# ferminator2000.net
KiCad netlist of a schematic drawn in EAGLE
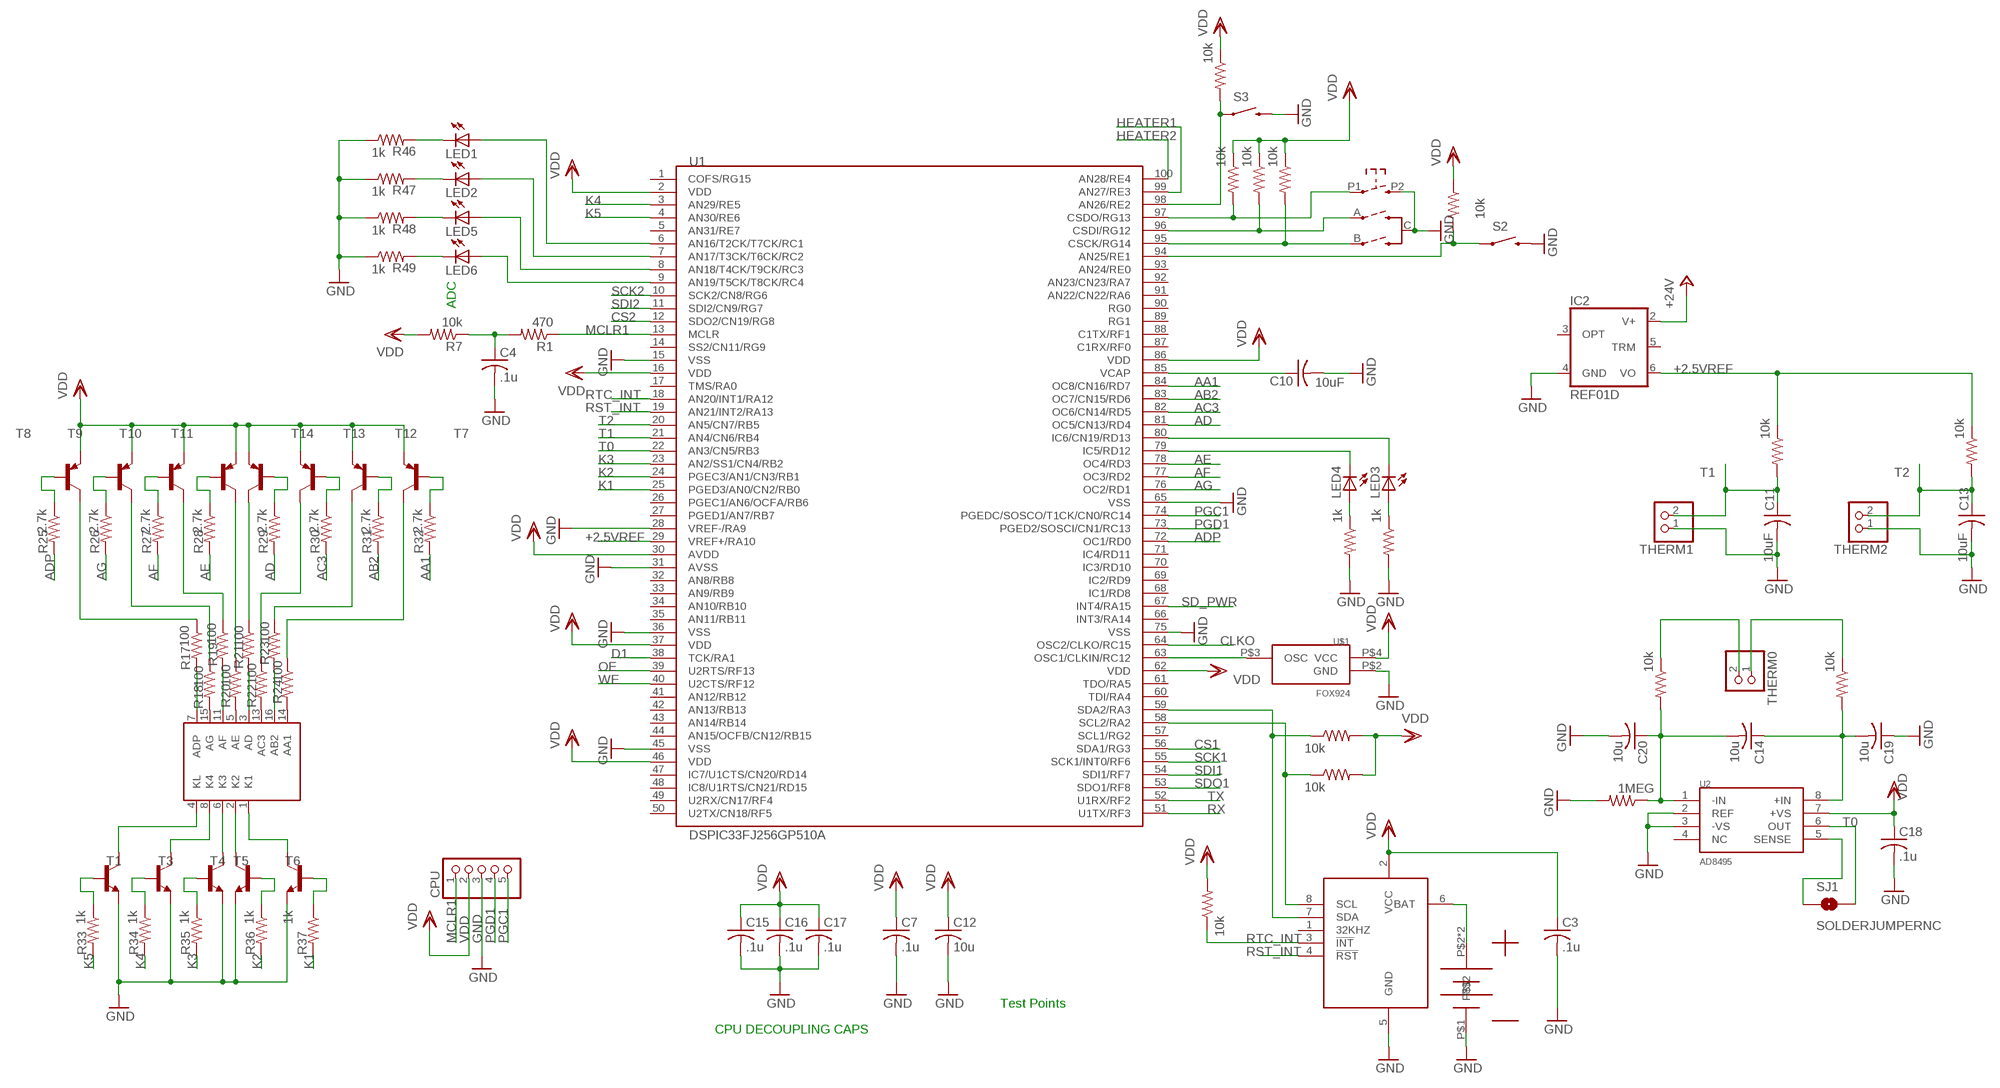
[diagram p0: schematic, sheet 1]
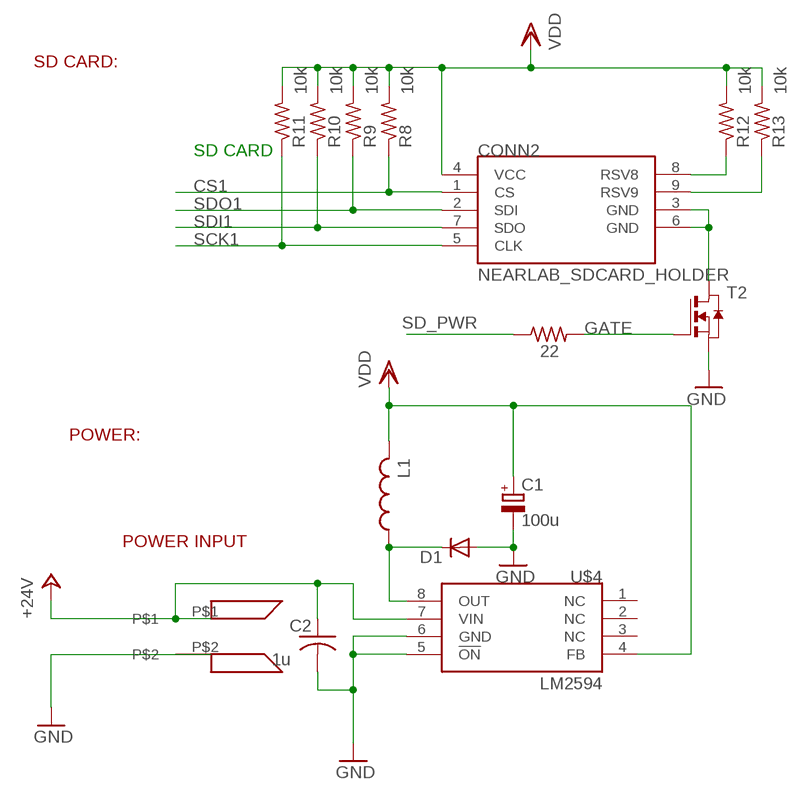
[diagram p1: schematic, sheet 2]
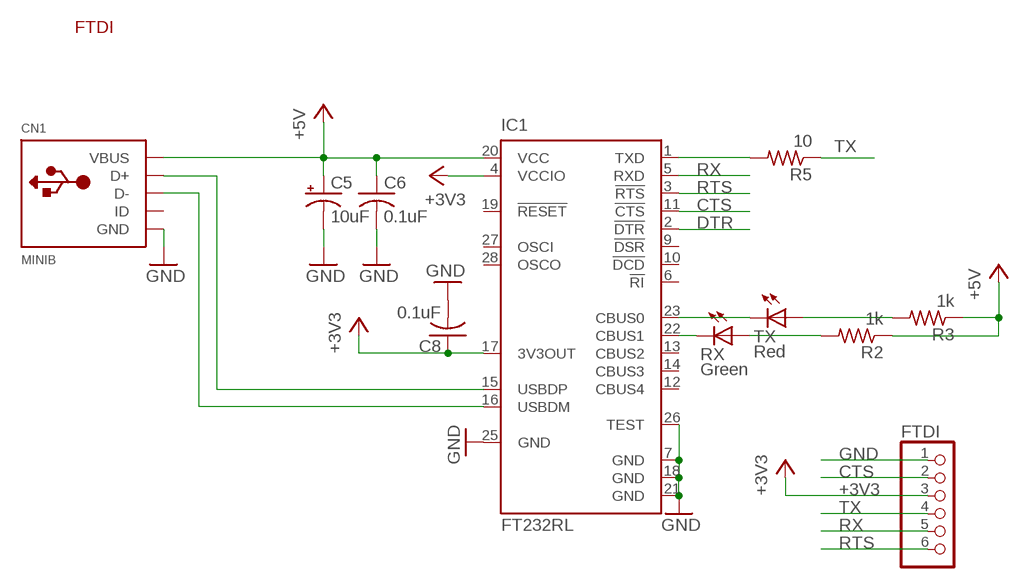
[diagram p2: schematic, sheet 3]
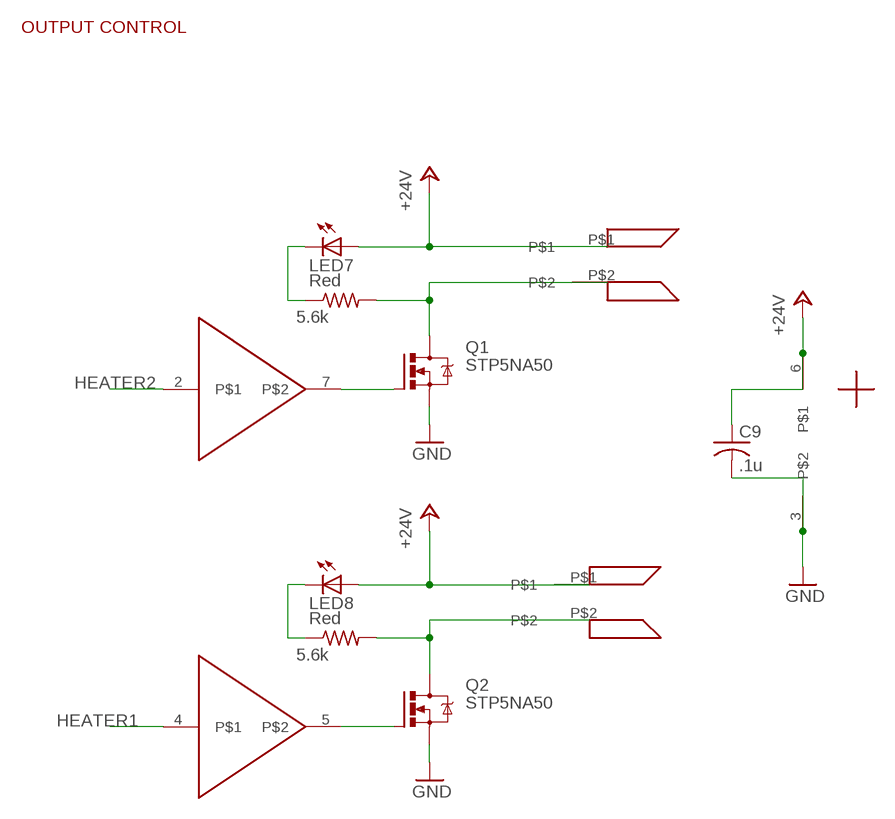
[diagram p3: schematic, sheet 4]

(export (version "E")
  (design (tool "Eeschema 10.0.6"))
  (components
    (comp (ref "C3")
      (value ".1u")
      (footprint "eagle-import:C0603")
      (libsource (lib "eagle-import") (part "rcl_C-USC0603"))
    )
    (comp (ref "C4")
      (value ".1u")
      (footprint "eagle-import:C0603")
      (libsource (lib "eagle-import") (part "rcl_C-USC0603"))
    )
    (comp (ref "C7")
      (value ".1u")
      (footprint "eagle-import:C0603")
      (libsource (lib "eagle-import") (part "rcl_C-USC0603"))
    )
    (comp (ref "C10")
      (value "10uF")
      (footprint "eagle-import:C0805")
      (libsource (lib "eagle-import") (part "rcl_C-USC0805"))
    )
    (comp (ref "C11")
      (value "10uF")
      (footprint "eagle-import:C0805")
      (libsource (lib "eagle-import") (part "rcl_C-USC0805"))
    )
    (comp (ref "C12")
      (value "10u")
      (footprint "eagle-import:C0805")
      (libsource (lib "eagle-import") (part "rcl_C-USC0805"))
    )
    (comp (ref "C13")
      (value "10uF")
      (footprint "eagle-import:C0805")
      (libsource (lib "eagle-import") (part "rcl_C-USC0805"))
    )
    (comp (ref "C14")
      (value "10u")
      (footprint "eagle-import:C0603")
      (libsource (lib "eagle-import") (part "rcl_C-USC0603"))
    )
    (comp (ref "C15")
      (value ".1u")
      (footprint "eagle-import:C0603")
      (libsource (lib "eagle-import") (part "rcl_C-USC0603"))
    )
    (comp (ref "C16")
      (value ".1u")
      (footprint "eagle-import:C0603")
      (libsource (lib "eagle-import") (part "rcl_C-USC0603"))
    )
    (comp (ref "C17")
      (value ".1u")
      (footprint "eagle-import:C0603")
      (libsource (lib "eagle-import") (part "rcl_C-USC0603"))
    )
    (comp (ref "C18")
      (value ".1u")
      (footprint "eagle-import:C0603")
      (libsource (lib "eagle-import") (part "rcl_C-USC0603"))
    )
    (comp (ref "C19")
      (value "10u")
      (footprint "eagle-import:C0603")
      (libsource (lib "eagle-import") (part "rcl_C-USC0603"))
    )
    (comp (ref "C20")
      (value "10u")
      (footprint "eagle-import:C0603")
      (libsource (lib "eagle-import") (part "rcl_C-USC0603"))
    )
    (comp (ref "CPU")
      (value "PINHD-1X5")
      (footprint "eagle-import:1X05")
      (libsource (lib "eagle-import") (part "PINHD-1X5"))
    )
    (comp (ref "IC2")
      (value "REF01D")
      (footprint "eagle-import:SO08")
      (libsource (lib "eagle-import") (part "REF01D"))
    )
    (comp (ref "LED1")
      (value "LEDCHIP-LED0805")
      (footprint "eagle-import:CHIP-LED0805")
      (libsource (lib "eagle-import") (part "led_LEDCHIP-LED0805"))
    )
    (comp (ref "LED2")
      (value "LEDCHIP-LED0805")
      (footprint "eagle-import:CHIP-LED0805")
      (libsource (lib "eagle-import") (part "led_LEDCHIP-LED0805"))
    )
    (comp (ref "LED3")
      (value "LEDCHIP-LED0805")
      (footprint "eagle-import:CHIP-LED0805")
      (libsource (lib "eagle-import") (part "led_LEDCHIP-LED0805"))
    )
    (comp (ref "LED4")
      (value "LEDCHIP-LED0805")
      (footprint "eagle-import:CHIP-LED0805")
      (libsource (lib "eagle-import") (part "led_LEDCHIP-LED0805"))
    )
    (comp (ref "LED5")
      (value "LEDCHIP-LED0805")
      (footprint "eagle-import:CHIP-LED0805")
      (libsource (lib "eagle-import") (part "led_LEDCHIP-LED0805"))
    )
    (comp (ref "LED6")
      (value "LEDCHIP-LED0805")
      (footprint "eagle-import:CHIP-LED0805")
      (libsource (lib "eagle-import") (part "led_LEDCHIP-LED0805"))
    )
    (comp (ref "R1")
      (value "470")
      (footprint "eagle-import:R0805")
      (libsource (lib "eagle-import") (part "rcl_R-US_R0805"))
    )
    (comp (ref "R7")
      (value "10k")
      (footprint "eagle-import:R0805")
      (libsource (lib "eagle-import") (part "rcl_R-US_R0805"))
    )
    (comp (ref "R14")
      (value "1k")
      (footprint "eagle-import:R0805")
      (libsource (lib "eagle-import") (part "rcl_R-US_R0805"))
    )
    (comp (ref "R15")
      (value "1k")
      (footprint "eagle-import:R0805")
      (libsource (lib "eagle-import") (part "rcl_R-US_R0805"))
    )
    (comp (ref "R17")
      (value "100")
      (footprint "eagle-import:R0805")
      (libsource (lib "eagle-import") (part "rcl_R-US_R0805"))
    )
    (comp (ref "R18")
      (value "100")
      (footprint "eagle-import:R0805")
      (libsource (lib "eagle-import") (part "rcl_R-US_R0805"))
    )
    (comp (ref "R19")
      (value "100")
      (footprint "eagle-import:R0805")
      (libsource (lib "eagle-import") (part "rcl_R-US_R0805"))
    )
    (comp (ref "R20")
      (value "100")
      (footprint "eagle-import:R0805")
      (libsource (lib "eagle-import") (part "rcl_R-US_R0805"))
    )
    (comp (ref "R21")
      (value "100")
      (footprint "eagle-import:R0805")
      (libsource (lib "eagle-import") (part "rcl_R-US_R0805"))
    )
    (comp (ref "R22")
      (value "100")
      (footprint "eagle-import:R0805")
      (libsource (lib "eagle-import") (part "rcl_R-US_R0805"))
    )
    (comp (ref "R23")
      (value "100")
      (footprint "eagle-import:R0805")
      (libsource (lib "eagle-import") (part "rcl_R-US_R0805"))
    )
    (comp (ref "R24")
      (value "100")
      (footprint "eagle-import:R0805")
      (libsource (lib "eagle-import") (part "rcl_R-US_R0805"))
    )
    (comp (ref "R25")
      (value "2.7k")
      (footprint "eagle-import:R0805")
      (libsource (lib "eagle-import") (part "rcl_R-US_R0805"))
    )
    (comp (ref "R26")
      (value "2.7k")
      (footprint "eagle-import:R0805")
      (libsource (lib "eagle-import") (part "rcl_R-US_R0805"))
    )
    (comp (ref "R27")
      (value "2.7k")
      (footprint "eagle-import:R0805")
      (libsource (lib "eagle-import") (part "rcl_R-US_R0805"))
    )
    (comp (ref "R28")
      (value "2.7k")
      (footprint "eagle-import:R0805")
      (libsource (lib "eagle-import") (part "rcl_R-US_R0805"))
    )
    (comp (ref "R29")
      (value "2.7k")
      (footprint "eagle-import:R0805")
      (libsource (lib "eagle-import") (part "rcl_R-US_R0805"))
    )
    (comp (ref "R30")
      (value "2.7k")
      (footprint "eagle-import:R0805")
      (libsource (lib "eagle-import") (part "rcl_R-US_R0805"))
    )
    (comp (ref "R31")
      (value "2.7k")
      (footprint "eagle-import:R0805")
      (libsource (lib "eagle-import") (part "rcl_R-US_R0805"))
    )
    (comp (ref "R32")
      (value "2.7k")
      (footprint "eagle-import:R0805")
      (libsource (lib "eagle-import") (part "rcl_R-US_R0805"))
    )
    (comp (ref "R33")
      (value "1k")
      (footprint "eagle-import:R0805")
      (libsource (lib "eagle-import") (part "rcl_R-US_R0805"))
    )
    (comp (ref "R34")
      (value "1k")
      (footprint "eagle-import:R0805")
      (libsource (lib "eagle-import") (part "rcl_R-US_R0805"))
    )
    (comp (ref "R35")
      (value "1k")
      (footprint "eagle-import:R0805")
      (libsource (lib "eagle-import") (part "rcl_R-US_R0805"))
    )
    (comp (ref "R36")
      (value "1k")
      (footprint "eagle-import:R0805")
      (libsource (lib "eagle-import") (part "rcl_R-US_R0805"))
    )
    (comp (ref "R37")
      (value "1k")
      (footprint "eagle-import:R0805")
      (libsource (lib "eagle-import") (part "rcl_R-US_R0805"))
    )
    (comp (ref "R38")
      (value "10k")
      (footprint "eagle-import:R0805")
      (libsource (lib "eagle-import") (part "rcl_R-US_R0805"))
    )
    (comp (ref "R39")
      (value "10k")
      (footprint "eagle-import:R0805")
      (libsource (lib "eagle-import") (part "rcl_R-US_R0805"))
    )
    (comp (ref "R40")
      (value "1MEG")
      (footprint "eagle-import:R0805")
      (libsource (lib "eagle-import") (part "rcl_R-US_R0805"))
    )
    (comp (ref "R41")
      (value "10k")
      (footprint "eagle-import:R0805")
      (libsource (lib "eagle-import") (part "rcl_R-US_R0805"))
    )
    (comp (ref "R42")
      (value "10k")
      (footprint "eagle-import:R0805")
      (libsource (lib "eagle-import") (part "rcl_R-US_R0805"))
    )
    (comp (ref "R43")
      (value "10k")
      (footprint "eagle-import:R0805")
      (libsource (lib "eagle-import") (part "rcl_R-US_R0805"))
    )
    (comp (ref "R44")
      (value "10k")
      (footprint "eagle-import:R0805")
      (libsource (lib "eagle-import") (part "rcl_R-US_R0805"))
    )
    (comp (ref "R45")
      (value "10k")
      (footprint "eagle-import:R0805")
      (libsource (lib "eagle-import") (part "rcl_R-US_R0805"))
    )
    (comp (ref "R46")
      (value "1k")
      (footprint "eagle-import:R0805")
      (libsource (lib "eagle-import") (part "rcl_R-US_R0805"))
    )
    (comp (ref "R47")
      (value "1k")
      (footprint "eagle-import:R0805")
      (libsource (lib "eagle-import") (part "rcl_R-US_R0805"))
    )
    (comp (ref "R48")
      (value "1k")
      (footprint "eagle-import:R0805")
      (libsource (lib "eagle-import") (part "rcl_R-US_R0805"))
    )
    (comp (ref "R49")
      (value "1k")
      (footprint "eagle-import:R0805")
      (libsource (lib "eagle-import") (part "rcl_R-US_R0805"))
    )
    (comp (ref "R50")
      (value "10k")
      (footprint "eagle-import:R0805")
      (libsource (lib "eagle-import") (part "rcl_R-US_R0805"))
    )
    (comp (ref "R51")
      (value "10k")
      (footprint "eagle-import:R0805")
      (libsource (lib "eagle-import") (part "rcl_R-US_R0805"))
    )
    (comp (ref "R52")
      (value "10k")
      (footprint "eagle-import:R0805")
      (libsource (lib "eagle-import") (part "rcl_R-US_R0805"))
    )
    (comp (ref "R53")
      (value "10k")
      (footprint "eagle-import:R0805")
      (libsource (lib "eagle-import") (part "rcl_R-US_R0805"))
    )
    (comp (ref "R54")
      (value "10k")
      (footprint "eagle-import:R0805")
      (libsource (lib "eagle-import") (part "rcl_R-US_R0805"))
    )
    (comp (ref "S2")
      (value "SWITCH-MOMENTARY-2")
      (footprint "eagle-import:TACTILE_SWITCH_TALL")
      (libsource (lib "eagle-import") (part "SWITCH-MOMENTARY-2"))
    )
    (comp (ref "S3")
      (value "SWITCH-MOMENTARY-2")
      (footprint "eagle-import:TACTILE_SWITCH_TALL")
      (libsource (lib "eagle-import") (part "SWITCH-MOMENTARY-2"))
    )
    (comp (ref "SJ1")
      (value "SOLDERJUMPERNC")
      (footprint "eagle-import:SJ_2S")
      (libsource (lib "eagle-import") (part "SOLDERJUMPERNC"))
    )
    (comp (ref "SW1")
      (value "ENCODER_SW1-PEC12")
      (footprint "eagle-import:PEC12_INCREMENTAL_ENCODER")
      (libsource (lib "eagle-import") (part "ENCODER_SW1-PEC12"))
    )
    (comp (ref "T1")
      (value "MMBT3904LT1-NPN-SOT23-BEC")
      (footprint "eagle-import:SOT23-BEC")
      (libsource (lib "eagle-import") (part "-NPN-SOT23-BECMMBT3904LT1"))
    )
    (comp (ref "T3")
      (value "MMBT3904LT1-NPN-SOT23-BEC")
      (footprint "eagle-import:SOT23-BEC")
      (libsource (lib "eagle-import") (part "-NPN-SOT23-BECMMBT3904LT1"))
    )
    (comp (ref "T4")
      (value "MMBT3904LT1-NPN-SOT23-BEC")
      (footprint "eagle-import:SOT23-BEC")
      (libsource (lib "eagle-import") (part "-NPN-SOT23-BECMMBT3904LT1"))
    )
    (comp (ref "T5")
      (value "MMBT3904LT1-NPN-SOT23-BEC")
      (footprint "eagle-import:SOT23-BEC")
      (libsource (lib "eagle-import") (part "-NPN-SOT23-BECMMBT3904LT1"))
    )
    (comp (ref "T6")
      (value "MMBT3904LT1-NPN-SOT23-BEC")
      (footprint "eagle-import:SOT23-BEC")
      (libsource (lib "eagle-import") (part "-NPN-SOT23-BECMMBT3904LT1"))
    )
    (comp (ref "T7")
      (value "MMBT3906LT1-PNP-SOT23-BEC")
      (footprint "eagle-import:SOT23-BEC")
      (libsource (lib "eagle-import") (part "-PNP-SOT23-BECMMBT3906LT1"))
    )
    (comp (ref "T8")
      (value "MMBT3906LT1-PNP-SOT23-BEC")
      (footprint "eagle-import:SOT23-BEC")
      (libsource (lib "eagle-import") (part "-PNP-SOT23-BECMMBT3906LT1"))
    )
    (comp (ref "T9")
      (value "MMBT3906LT1-PNP-SOT23-BEC")
      (footprint "eagle-import:SOT23-BEC")
      (libsource (lib "eagle-import") (part "-PNP-SOT23-BECMMBT3906LT1"))
    )
    (comp (ref "T10")
      (value "MMBT3906LT1-PNP-SOT23-BEC")
      (footprint "eagle-import:SOT23-BEC")
      (libsource (lib "eagle-import") (part "-PNP-SOT23-BECMMBT3906LT1"))
    )
    (comp (ref "T11")
      (value "MMBT3906LT1-PNP-SOT23-BEC")
      (footprint "eagle-import:SOT23-BEC")
      (libsource (lib "eagle-import") (part "-PNP-SOT23-BECMMBT3906LT1"))
    )
    (comp (ref "T12")
      (value "MMBT3906LT1-PNP-SOT23-BEC")
      (footprint "eagle-import:SOT23-BEC")
      (libsource (lib "eagle-import") (part "-PNP-SOT23-BECMMBT3906LT1"))
    )
    (comp (ref "T13")
      (value "MMBT3906LT1-PNP-SOT23-BEC")
      (footprint "eagle-import:SOT23-BEC")
      (libsource (lib "eagle-import") (part "-PNP-SOT23-BECMMBT3906LT1"))
    )
    (comp (ref "T14")
      (value "MMBT3906LT1-PNP-SOT23-BEC")
      (footprint "eagle-import:SOT23-BEC")
      (libsource (lib "eagle-import") (part "-PNP-SOT23-BECMMBT3906LT1"))
    )
    (comp (ref "THERM0")
      (value "PINHD-1X2")
      (footprint "eagle-import:1X02")
      (libsource (lib "eagle-import") (part "PINHD-1X2"))
    )
    (comp (ref "THERM1")
      (value "PINHD-1X2")
      (footprint "eagle-import:1X02")
      (libsource (lib "eagle-import") (part "PINHD-1X2"))
    )
    (comp (ref "THERM2")
      (value "PINHD-1X2")
      (footprint "eagle-import:1X02")
      (libsource (lib "eagle-import") (part "PINHD-1X2"))
    )
    (comp (ref "U$1")
      (value "FOX924")
      (footprint "eagle-import:CRYSTAL")
      (libsource (lib "eagle-import") (part "FOX924"))
    )
    (comp (ref "U$2")
      (value "12MM_BATTER_HOLDER")
      (footprint "eagle-import:12.5MMCOILCELLHOLDER")
      (libsource (lib "eagle-import") (part "12MM_BATTER_HOLDER"))
    )
    (comp (ref "U$5")
      (value "DS3231")
      (footprint "eagle-import:SOIC8")
      (libsource (lib "eagle-import") (part "DS3231"))
    )
    (comp (ref "U$7")
      (value "LTC-4027JRLTC-4027JR")
      (footprint "eagle-import:LTC-4727JR")
      (libsource (lib "eagle-import") (part "LTC-4027JRLTC-4027JR"))
    )
    (comp (ref "U1")
      (value "DSPIC33FJ256GP510A")
      (footprint "eagle-import:TQFP100")
      (libsource (lib "eagle-import") (part "DSPIC33FJ256GP510A"))
    )
    (comp (ref "U2")
      (value "AD8495")
      (footprint "eagle-import:MSOP8")
      (libsource (lib "eagle-import") (part "AD8497"))
    )
    (comp (ref "C1")
      (value "100u")
      (footprint "eagle-import:UD-6,3X5,8_NICHICON")
      (libsource (lib "eagle-import") (part "CPOL-EUUD-6,3X8,8"))
    )
    (comp (ref "C2")
      (value "1u")
      (footprint "eagle-import:C0805")
      (libsource (lib "eagle-import") (part "rcl_C-USC0805"))
    )
    (comp (ref "CONN2")
      (value "NEARLAB_SDCARD_HOLDER")
      (footprint "eagle-import:NEARLAB_DM1AA-SF-PEJ")
      (libsource (lib "eagle-import") (part "NEARLAB_SDCARD_HOLDER"))
    )
    (comp (ref "D1")
      (value "DIODE-SOD323-R")
      (footprint "eagle-import:SOD323-R")
      (libsource (lib "eagle-import") (part "DIODE-SOD323-R"))
    )
    (comp (ref "L1")
      (value "L-USL3225M")
      (footprint "eagle-import:L3225M")
      (libsource (lib "eagle-import") (part "L-USL3225M"))
    )
    (comp (ref "R8")
      (value "10k")
      (footprint "eagle-import:R0805")
      (libsource (lib "eagle-import") (part "rcl_R-US_R0805"))
    )
    (comp (ref "R9")
      (value "10k")
      (footprint "eagle-import:R0805")
      (libsource (lib "eagle-import") (part "rcl_R-US_R0805"))
    )
    (comp (ref "R10")
      (value "10k")
      (footprint "eagle-import:R0805")
      (libsource (lib "eagle-import") (part "rcl_R-US_R0805"))
    )
    (comp (ref "R11")
      (value "10k")
      (footprint "eagle-import:R0805")
      (libsource (lib "eagle-import") (part "rcl_R-US_R0805"))
    )
    (comp (ref "R12")
      (value "10k")
      (footprint "eagle-import:R0805")
      (libsource (lib "eagle-import") (part "rcl_R-US_R0805"))
    )
    (comp (ref "R13")
      (value "10k")
      (footprint "eagle-import:R0805")
      (libsource (lib "eagle-import") (part "rcl_R-US_R0805"))
    )
    (comp (ref "R16")
      (value "22")
      (footprint "eagle-import:R0805")
      (libsource (lib "eagle-import") (part "rcl_R-US_R0805"))
    )
    (comp (ref "T2")
      (value "NMOSSOT23")
      (footprint "eagle-import:SOT-23")
      (libsource (lib "eagle-import") (part "NMOSSOT23"))
    )
    (comp (ref "U$3")
      (value "PHOENIX-3.5MM")
      (footprint "eagle-import:PHOENIX_3.5MM")
      (libsource (lib "eagle-import") (part "PHOENIX-3.5MM"))
    )
    (comp (ref "U$4")
      (value "LM2594")
      (footprint "eagle-import:SOIC8")
      (libsource (lib "eagle-import") (part "LM2594"))
    )
    (comp (ref "C9")
      (value ".1u")
      (footprint "eagle-import:C0603")
      (libsource (lib "eagle-import") (part "rcl_C-USC0603"))
    )
    (comp (ref "LED7")
      (value "Red")
      (footprint "eagle-import:CHIP-LED0805")
      (libsource (lib "eagle-import") (part "LEDCHIP-LED0805"))
    )
    (comp (ref "LED8")
      (value "Red")
      (footprint "eagle-import:CHIP-LED0805")
      (libsource (lib "eagle-import") (part "LEDCHIP-LED0805"))
    )
    (comp (ref "Q1")
      (value "STP5NA50")
      (footprint "eagle-import:TO220BV")
      (libsource (lib "eagle-import") (part "STP5NA50"))
    )
    (comp (ref "Q2")
      (value "STP5NA50")
      (footprint "eagle-import:TO220BV")
      (libsource (lib "eagle-import") (part "STP5NA50"))
    )
    (comp (ref "R4")
      (value "5.6k")
      (footprint "eagle-import:R0805")
      (libsource (lib "eagle-import") (part "rcl_R-US_R0805"))
    )
    (comp (ref "R6")
      (value "5.6k")
      (footprint "eagle-import:R0805")
      (libsource (lib "eagle-import") (part "rcl_R-US_R0805"))
    )
    (comp (ref "U$8")
      (value "PHOENIX-3.5MM")
      (footprint "eagle-import:PHOENIX_3.5MM")
      (libsource (lib "eagle-import") (part "PHOENIX-3.5MM"))
    )
    (comp (ref "U$10")
      (value "PHOENIX-3.5MM")
      (footprint "eagle-import:PHOENIX_3.5MM")
      (libsource (lib "eagle-import") (part "PHOENIX-3.5MM"))
    )
    (comp (ref "U$11")
      (value "TC4427")
      (footprint "eagle-import:SOIC8")
      (libsource (lib "eagle-import") (part "TC4427"))
    )
    (comp (ref "C5")
      (value "10uF")
      (footprint "eagle-import:A_3216-18R")
      (libsource (lib "eagle-import") (part "CPOL-USA/3216-18R"))
    )
    (comp (ref "C6")
      (value "0.1uF")
      (footprint "eagle-import:C0805K")
      (libsource (lib "eagle-import") (part "C-USC0805K"))
    )
    (comp (ref "C8")
      (value "0.1uF")
      (footprint "eagle-import:C0805K")
      (libsource (lib "eagle-import") (part "C-USC0805K"))
    )
    (comp (ref "CN1")
      (value "MINIB")
      (footprint "eagle-import:USB-MINIB")
      (libsource (lib "eagle-import") (part "USBMINIB"))
    )
    (comp (ref "FTDI")
      (value "PINHD-1X6CB")
      (footprint "eagle-import:1X06-CLEANBIG")
      (libsource (lib "eagle-import") (part "PINHD-1X6CB"))
    )
    (comp (ref "IC1")
      (value "FT232RL")
      (footprint "eagle-import:SSOP28")
      (libsource (lib "eagle-import") (part "FT232RL"))
    )
    (comp (ref "R2")
      (value "1k")
      (footprint "eagle-import:R0805")
      (libsource (lib "eagle-import") (part "R-US_R0805"))
    )
    (comp (ref "R3")
      (value "1k")
      (footprint "eagle-import:R0805")
      (libsource (lib "eagle-import") (part "R-US_R0805"))
    )
    (comp (ref "R5")
      (value "10")
      (footprint "eagle-import:R0805")
      (libsource (lib "eagle-import") (part "R-US_R0805"))
    )
    (comp (ref "RX")
      (value "Green")
      (footprint "eagle-import:CHIP-LED0805")
      (libsource (lib "eagle-import") (part "LEDCHIP-LED0805"))
    )
    (comp (ref "TX")
      (value "Red")
      (footprint "eagle-import:CHIP-LED0805")
      (libsource (lib "eagle-import") (part "LEDCHIP-LED0805"))
    )
  )
  (nets
    (net (code "1") (name "+2.5VREF") (class "Default")
      (node (ref "IC2") (pin "6") (pinfunction "VO_6") (pintype "output"))
      (node (ref "R38") (pin "1") (pinfunction "1_1") (pintype "passive"))
      (node (ref "R39") (pin "1") (pinfunction "1_1") (pintype "passive"))
      (node (ref "U1") (pin "29") (pinfunction "VREF+/RA10_29") (pintype "bidirectional"))
    )
    (net (code "2") (name "+3V3") (class "Default")
      (node (ref "C8") (pin "1") (pinfunction "1_1") (pintype "passive"))
      (node (ref "FTDI") (pin "3") (pinfunction "3_3") (pintype "passive"))
      (node (ref "IC1") (pin "17") (pinfunction "3V3OUT_17") (pintype "output"))
      (node (ref "IC1") (pin "4") (pinfunction "VCCIO_4") (pintype "power_in"))
    )
    (net (code "3") (name "+5V") (class "Default")
      (node (ref "C5") (pin "+") (pinfunction "+_+") (pintype "passive"))
      (node (ref "C6") (pin "1") (pinfunction "1_1") (pintype "passive"))
      (node (ref "CN1") (pin "VBUS") (pinfunction "VBUS_VBUS") (pintype "power_in"))
      (node (ref "IC1") (pin "20") (pinfunction "VCC_20") (pintype "power_in"))
      (node (ref "R2") (pin "1") (pinfunction "1_1") (pintype "passive"))
      (node (ref "R3") (pin "1") (pinfunction "1_1") (pintype "passive"))
    )
    (net (code "4") (name "+24V") (class "Default")
      (node (ref "C2") (pin "1") (pinfunction "1_1") (pintype "passive"))
      (node (ref "C9") (pin "1") (pinfunction "1_1") (pintype "passive"))
      (node (ref "IC2") (pin "2") (pinfunction "V+_2") (pintype "power_in"))
      (node (ref "LED7") (pin "A") (pinfunction "A_A") (pintype "passive"))
      (node (ref "LED8") (pin "A") (pinfunction "A_A") (pintype "passive"))
      (node (ref "U$10") (pin "P$1") (pinfunction "P$1_P$1") (pintype "bidirectional"))
      (node (ref "U$11") (pin "6") (pinfunction "P$1_6") (pintype "bidirectional"))
      (node (ref "U$3") (pin "P$1") (pinfunction "P$1_P$1") (pintype "bidirectional"))
      (node (ref "U$4") (pin "7") (pinfunction "VIN_7") (pintype "bidirectional"))
      (node (ref "U$8") (pin "P$1") (pinfunction "P$1_P$1") (pintype "bidirectional"))
    )
    (net (code "5") (name "AA1") (class "Default")
      (node (ref "R32") (pin "2") (pinfunction "2_2") (pintype "passive"))
      (node (ref "U1") (pin "84") (pinfunction "OC8/CN16/RD7_84") (pintype "bidirectional"))
    )
    (net (code "6") (name "AB2") (class "Default")
      (node (ref "R31") (pin "2") (pinfunction "2_2") (pintype "passive"))
      (node (ref "U1") (pin "83") (pinfunction "OC7/CN15/RD6_83") (pintype "bidirectional"))
    )
    (net (code "7") (name "AC3") (class "Default")
      (node (ref "R30") (pin "2") (pinfunction "2_2") (pintype "passive"))
      (node (ref "U1") (pin "82") (pinfunction "OC6/CN14/RD5_82") (pintype "bidirectional"))
    )
    (net (code "8") (name "AD") (class "Default")
      (node (ref "R29") (pin "2") (pinfunction "2_2") (pintype "passive"))
      (node (ref "U1") (pin "81") (pinfunction "OC5/CN13/RD4_81") (pintype "bidirectional"))
    )
    (net (code "9") (name "ADP") (class "Default")
      (node (ref "R25") (pin "2") (pinfunction "2_2") (pintype "passive"))
      (node (ref "U1") (pin "72") (pinfunction "OC1/RD0_72") (pintype "bidirectional"))
    )
    (net (code "10") (name "AE") (class "Default")
      (node (ref "R28") (pin "2") (pinfunction "2_2") (pintype "passive"))
      (node (ref "U1") (pin "78") (pinfunction "OC4/RD3_78") (pintype "bidirectional"))
    )
    (net (code "11") (name "AF") (class "Default")
      (node (ref "R27") (pin "2") (pinfunction "2_2") (pintype "passive"))
      (node (ref "U1") (pin "77") (pinfunction "OC3/RD2_77") (pintype "bidirectional"))
    )
    (net (code "12") (name "AG") (class "Default")
      (node (ref "R26") (pin "2") (pinfunction "2_2") (pintype "passive"))
      (node (ref "U1") (pin "76") (pinfunction "OC2/RD1_76") (pintype "bidirectional"))
    )
    (net (code "13") (name "CLKO") (class "Default")
      (node (ref "U1") (pin "64") (pinfunction "OSC2/CLKO/RC15_64") (pintype "bidirectional"))
    )
    (net (code "14") (name "CS1") (class "Default")
      (node (ref "CONN2") (pin "1") (pinfunction "CS_1") (pintype "bidirectional"))
      (node (ref "R8") (pin "1") (pinfunction "1_1") (pintype "passive"))
      (node (ref "U1") (pin "56") (pinfunction "SDA1/RG3_56") (pintype "bidirectional"))
    )
    (net (code "15") (name "CS2") (class "Default")
      (node (ref "U1") (pin "12") (pinfunction "SDO2/CN19/RG8_12") (pintype "bidirectional"))
    )
    (net (code "16") (name "CTS") (class "Default")
      (node (ref "FTDI") (pin "2") (pinfunction "2_2") (pintype "passive"))
      (node (ref "IC1") (pin "11") (pinfunction "~{CTS}_11") (pintype "input"))
    )
    (net (code "17") (name "D1") (class "Default")
      (node (ref "U1") (pin "38") (pinfunction "TCK/RA1_38") (pintype "bidirectional"))
    )
    (net (code "18") (name "DTR") (class "Default")
      (node (ref "IC1") (pin "2") (pinfunction "~{DTR}_2") (pintype "output"))
    )
    (net (code "19") (name "GATE") (class "Default")
      (node (ref "R16") (pin "2") (pinfunction "2_2") (pintype "passive"))
      (node (ref "T2") (pin "3") (pinfunction "G_3") (pintype "passive"))
    )
    (net (code "20") (name "GND") (class "Default")
      (node (ref "C1") (pin "-") (pinfunction "-_-") (pintype "passive"))
      (node (ref "C10") (pin "2") (pinfunction "2_2") (pintype "passive"))
      (node (ref "C11") (pin "2") (pinfunction "2_2") (pintype "passive"))
      (node (ref "C12") (pin "2") (pinfunction "2_2") (pintype "passive"))
      (node (ref "C13") (pin "2") (pinfunction "2_2") (pintype "passive"))
      (node (ref "C15") (pin "2") (pinfunction "2_2") (pintype "passive"))
      (node (ref "C16") (pin "2") (pinfunction "2_2") (pintype "passive"))
      (node (ref "C17") (pin "2") (pinfunction "2_2") (pintype "passive"))
      (node (ref "C18") (pin "2") (pinfunction "2_2") (pintype "passive"))
      (node (ref "C19") (pin "1") (pinfunction "1_1") (pintype "passive"))
      (node (ref "C2") (pin "2") (pinfunction "2_2") (pintype "passive"))
      (node (ref "C20") (pin "2") (pinfunction "2_2") (pintype "passive"))
      (node (ref "C3") (pin "2") (pinfunction "2_2") (pintype "passive"))
      (node (ref "C4") (pin "2") (pinfunction "2_2") (pintype "passive"))
      (node (ref "C5") (pin "-") (pinfunction "-_-") (pintype "passive"))
      (node (ref "C6") (pin "2") (pinfunction "2_2") (pintype "passive"))
      (node (ref "C7") (pin "2") (pinfunction "2_2") (pintype "passive"))
      (node (ref "C8") (pin "2") (pinfunction "2_2") (pintype "passive"))
      (node (ref "C9") (pin "2") (pinfunction "2_2") (pintype "passive"))
      (node (ref "CN1") (pin "GND") (pinfunction "GND_GND") (pintype "power_in"))
      (node (ref "CPU") (pin "3") (pinfunction "3_3") (pintype "passive"))
      (node (ref "D1") (pin "A") (pinfunction "A_A") (pintype "passive"))
      (node (ref "FTDI") (pin "1") (pinfunction "1_1") (pintype "passive"))
      (node (ref "IC1") (pin "18") (pinfunction "GND_18") (pintype "power_in"))
      (node (ref "IC1") (pin "21") (pinfunction "GND_21") (pintype "power_in"))
      (node (ref "IC1") (pin "25") (pinfunction "GND_25") (pintype "power_in"))
      (node (ref "IC1") (pin "26") (pinfunction "TEST_26") (pintype "input"))
      (node (ref "IC1") (pin "7") (pinfunction "GND_7") (pintype "power_in"))
      (node (ref "IC2") (pin "4") (pinfunction "GND_4") (pintype "power_in"))
      (node (ref "Q1") (pin "S") (pinfunction "S_S") (pintype "passive"))
      (node (ref "Q2") (pin "S") (pinfunction "S_S") (pintype "passive"))
      (node (ref "R14") (pin "2") (pinfunction "2_2") (pintype "passive"))
      (node (ref "R15") (pin "2") (pinfunction "2_2") (pintype "passive"))
      (node (ref "R40") (pin "2") (pinfunction "2_2") (pintype "passive"))
      (node (ref "R46") (pin "1") (pinfunction "1_1") (pintype "passive"))
      (node (ref "R47") (pin "1") (pinfunction "1_1") (pintype "passive"))
      (node (ref "R48") (pin "1") (pinfunction "1_1") (pintype "passive"))
      (node (ref "R49") (pin "1") (pinfunction "1_1") (pintype "passive"))
      (node (ref "S2") (pin "B2") (pinfunction "2_B2") (pintype "passive"))
      (node (ref "S3") (pin "B2") (pinfunction "2_B2") (pintype "passive"))
      (node (ref "SW1") (pin "C") (pinfunction "C_C") (pintype "passive"))
      (node (ref "SW1") (pin "P2") (pinfunction "2_P2") (pintype "passive"))
      (node (ref "T1") (pin "E") (pinfunction "E_E") (pintype "passive"))
      (node (ref "T2") (pin "2") (pinfunction "S_2") (pintype "passive"))
      (node (ref "T3") (pin "E") (pinfunction "E_E") (pintype "passive"))
      (node (ref "T4") (pin "E") (pinfunction "E_E") (pintype "passive"))
      (node (ref "T5") (pin "E") (pinfunction "E_E") (pintype "passive"))
      (node (ref "T6") (pin "E") (pinfunction "E_E") (pintype "passive"))
      (node (ref "THERM1") (pin "1") (pinfunction "1_1") (pintype "passive"))
      (node (ref "THERM2") (pin "1") (pinfunction "1_1") (pintype "passive"))
      (node (ref "U$1") (pin "P$2") (pinfunction "GND_P$2") (pintype "bidirectional"))
      (node (ref "U$11") (pin "3") (pinfunction "P$2_3") (pintype "bidirectional"))
      (node (ref "U$2") (pin "P$1") (pinfunction "P$2_P$1") (pintype "bidirectional"))
      (node (ref "U$3") (pin "P$2") (pinfunction "P$2_P$2") (pintype "bidirectional"))
      (node (ref "U$4") (pin "5") (pinfunction "~{ON}_5") (pintype "bidirectional"))
      (node (ref "U$4") (pin "6") (pinfunction "GND_6") (pintype "bidirectional"))
      (node (ref "U$5") (pin "5") (pinfunction "GND_5") (pintype "bidirectional"))
      (node (ref "U1") (pin "15") (pinfunction "VSS_15") (pintype "bidirectional"))
      (node (ref "U1") (pin "28") (pinfunction "VREF-/RA9_28") (pintype "bidirectional"))
      (node (ref "U1") (pin "31") (pinfunction "AVSS_31") (pintype "bidirectional"))
      (node (ref "U1") (pin "36") (pinfunction "VSS_36") (pintype "bidirectional"))
      (node (ref "U1") (pin "45") (pinfunction "VSS_45") (pintype "bidirectional"))
      (node (ref "U1") (pin "65") (pinfunction "VSS_65") (pintype "bidirectional"))
      (node (ref "U1") (pin "75") (pinfunction "VSS_75") (pintype "bidirectional"))
      (node (ref "U2") (pin "2") (pinfunction "REF_2") (pintype "bidirectional"))
      (node (ref "U2") (pin "3") (pinfunction "-VS_3") (pintype "bidirectional"))
    )
    (net (code "21") (name "HEATER1") (class "Default")
      (node (ref "U$11") (pin "4") (pinfunction "P$1_4") (pintype "bidirectional"))
      (node (ref "U1") (pin "99") (pinfunction "AN27/RE3_99") (pintype "bidirectional"))
    )
    (net (code "22") (name "HEATER2") (class "Default")
      (node (ref "U$11") (pin "2") (pinfunction "P$1_2") (pintype "bidirectional"))
      (node (ref "U1") (pin "100") (pinfunction "AN28/RE4_100") (pintype "bidirectional"))
    )
    (net (code "23") (name "K1") (class "Default")
      (node (ref "R37") (pin "2") (pinfunction "2_2") (pintype "passive"))
      (node (ref "U1") (pin "25") (pinfunction "PGED3/AN0/CN2/RB0_25") (pintype "bidirectional"))
    )
    (net (code "24") (name "K2") (class "Default")
      (node (ref "R36") (pin "2") (pinfunction "2_2") (pintype "passive"))
      (node (ref "U1") (pin "24") (pinfunction "PGEC3/AN1/CN3/RB1_24") (pintype "bidirectional"))
    )
    (net (code "25") (name "K3") (class "Default")
      (node (ref "R35") (pin "2") (pinfunction "2_2") (pintype "passive"))
      (node (ref "U1") (pin "23") (pinfunction "AN2/SS1/CN4/RB2_23") (pintype "bidirectional"))
    )
    (net (code "26") (name "K4") (class "Default")
      (node (ref "R34") (pin "2") (pinfunction "2_2") (pintype "passive"))
      (node (ref "U1") (pin "3") (pinfunction "AN29/RE5_3") (pintype "bidirectional"))
    )
    (net (code "27") (name "K5") (class "Default")
      (node (ref "R33") (pin "2") (pinfunction "2_2") (pintype "passive"))
      (node (ref "U1") (pin "4") (pinfunction "AN30/RE6_4") (pintype "bidirectional"))
    )
    (net (code "28") (name "MCLR1") (class "Default")
      (node (ref "CPU") (pin "1") (pinfunction "1_1") (pintype "passive"))
      (node (ref "R1") (pin "1") (pinfunction "1_1") (pintype "passive"))
      (node (ref "U1") (pin "13") (pinfunction "MCLR_13") (pintype "bidirectional"))
    )
    (net (code "29") (name "Net-(C4-Pad1)") (class "Default")
      (node (ref "C4") (pin "1") (pinfunction "1_1") (pintype "passive"))
      (node (ref "R1") (pin "2") (pinfunction "2_2") (pintype "passive"))
      (node (ref "R7") (pin "1") (pinfunction "1_1") (pintype "passive"))
    )
    (net (code "30") (name "Net-(CONN2-RSV8)") (class "Default")
      (node (ref "CONN2") (pin "8") (pinfunction "RSV8_8") (pintype "bidirectional"))
      (node (ref "R12") (pin "1") (pinfunction "1_1") (pintype "passive"))
    )
    (net (code "31") (name "Net-(CONN2-RSV9)") (class "Default")
      (node (ref "CONN2") (pin "9") (pinfunction "RSV9_9") (pintype "bidirectional"))
      (node (ref "R13") (pin "1") (pinfunction "1_1") (pintype "passive"))
    )
    (net (code "32") (name "Net-(IC1-CBUS0)") (class "Default")
      (node (ref "IC1") (pin "23") (pinfunction "CBUS0_23") (pintype "bidirectional"))
      (node (ref "TX") (pin "C") (pinfunction "C_C") (pintype "passive"))
    )
    (net (code "33") (name "Net-(IC1-CBUS1)") (class "Default")
      (node (ref "IC1") (pin "22") (pinfunction "CBUS1_22") (pintype "bidirectional"))
      (node (ref "RX") (pin "C") (pinfunction "C_C") (pintype "passive"))
    )
    (net (code "34") (name "Net-(IC1-TXD)") (class "Default")
      (node (ref "IC1") (pin "1") (pinfunction "TXD_1") (pintype "output"))
      (node (ref "R5") (pin "2") (pinfunction "2_2") (pintype "passive"))
    )
    (net (code "35") (name "Net-(IC1-USBDM)") (class "Default")
      (node (ref "CN1") (pin "D-") (pinfunction "D-_D-") (pintype "bidirectional"))
      (node (ref "IC1") (pin "16") (pinfunction "USBDM_16") (pintype "bidirectional"))
    )
    (net (code "36") (name "Net-(IC1-USBDP)") (class "Default")
      (node (ref "CN1") (pin "D+") (pinfunction "D+_D+") (pintype "bidirectional"))
      (node (ref "IC1") (pin "15") (pinfunction "USBDP_15") (pintype "bidirectional"))
    )
    (net (code "37") (name "Net-(LED1-PadC)") (class "Default")
      (node (ref "LED1") (pin "C") (pinfunction "C_C") (pintype "passive"))
      (node (ref "R46") (pin "2") (pinfunction "2_2") (pintype "passive"))
    )
    (net (code "38") (name "Net-(LED2-PadC)") (class "Default")
      (node (ref "LED2") (pin "C") (pinfunction "C_C") (pintype "passive"))
      (node (ref "R47") (pin "2") (pinfunction "2_2") (pintype "passive"))
    )
    (net (code "39") (name "Net-(LED3-PadA)") (class "Default")
      (node (ref "LED3") (pin "A") (pinfunction "A_A") (pintype "passive"))
      (node (ref "R14") (pin "1") (pinfunction "1_1") (pintype "passive"))
    )
    (net (code "40") (name "Net-(LED4-PadA)") (class "Default")
      (node (ref "LED4") (pin "A") (pinfunction "A_A") (pintype "passive"))
      (node (ref "R15") (pin "1") (pinfunction "1_1") (pintype "passive"))
    )
    (net (code "41") (name "Net-(LED5-PadC)") (class "Default")
      (node (ref "LED5") (pin "C") (pinfunction "C_C") (pintype "passive"))
      (node (ref "R48") (pin "2") (pinfunction "2_2") (pintype "passive"))
    )
    (net (code "42") (name "Net-(LED6-PadC)") (class "Default")
      (node (ref "LED6") (pin "C") (pinfunction "C_C") (pintype "passive"))
      (node (ref "R49") (pin "2") (pinfunction "2_2") (pintype "passive"))
    )
    (net (code "43") (name "Net-(LED7-PadC)") (class "Default")
      (node (ref "LED7") (pin "C") (pinfunction "C_C") (pintype "passive"))
      (node (ref "R4") (pin "1") (pinfunction "1_1") (pintype "passive"))
    )
    (net (code "44") (name "Net-(LED8-PadC)") (class "Default")
      (node (ref "LED8") (pin "C") (pinfunction "C_C") (pintype "passive"))
      (node (ref "R6") (pin "1") (pinfunction "1_1") (pintype "passive"))
    )
    (net (code "45") (name "Net-(Q1-PadD)") (class "Default")
      (node (ref "Q1") (pin "D") (pinfunction "D_D") (pintype "passive"))
      (node (ref "R4") (pin "2") (pinfunction "2_2") (pintype "passive"))
      (node (ref "U$10") (pin "P$2") (pinfunction "P$2_P$2") (pintype "bidirectional"))
    )
    (net (code "46") (name "Net-(Q2-PadD)") (class "Default")
      (node (ref "Q2") (pin "D") (pinfunction "D_D") (pintype "passive"))
      (node (ref "R6") (pin "2") (pinfunction "2_2") (pintype "passive"))
      (node (ref "U$8") (pin "P$2") (pinfunction "P$2_P$2") (pintype "bidirectional"))
    )
    (net (code "47") (name "Net-(R2-Pad2)") (class "Default")
      (node (ref "R2") (pin "2") (pinfunction "2_2") (pintype "passive"))
      (node (ref "RX") (pin "A") (pinfunction "A_A") (pintype "passive"))
    )
    (net (code "48") (name "Net-(R3-Pad2)") (class "Default")
      (node (ref "R3") (pin "2") (pinfunction "2_2") (pintype "passive"))
      (node (ref "TX") (pin "A") (pinfunction "A_A") (pintype "passive"))
    )
    (net (code "49") (name "Net-(R17-Pad1)") (class "Default")
      (node (ref "R17") (pin "1") (pinfunction "1_1") (pintype "passive"))
      (node (ref "T8") (pin "C") (pinfunction "C_C") (pintype "passive"))
    )
    (net (code "50") (name "Net-(R18-Pad1)") (class "Default")
      (node (ref "R18") (pin "1") (pinfunction "1_1") (pintype "passive"))
      (node (ref "T9") (pin "C") (pinfunction "C_C") (pintype "passive"))
    )
    (net (code "51") (name "Net-(R19-Pad1)") (class "Default")
      (node (ref "R19") (pin "1") (pinfunction "1_1") (pintype "passive"))
      (node (ref "T10") (pin "C") (pinfunction "C_C") (pintype "passive"))
    )
    (net (code "52") (name "Net-(R20-Pad1)") (class "Default")
      (node (ref "R20") (pin "1") (pinfunction "1_1") (pintype "passive"))
      (node (ref "T11") (pin "C") (pinfunction "C_C") (pintype "passive"))
    )
    (net (code "53") (name "Net-(R21-Pad1)") (class "Default")
      (node (ref "R21") (pin "1") (pinfunction "1_1") (pintype "passive"))
      (node (ref "T14") (pin "C") (pinfunction "C_C") (pintype "passive"))
    )
    (net (code "54") (name "Net-(R22-Pad1)") (class "Default")
      (node (ref "R22") (pin "1") (pinfunction "1_1") (pintype "passive"))
      (node (ref "T13") (pin "C") (pinfunction "C_C") (pintype "passive"))
    )
    (net (code "55") (name "Net-(R23-Pad1)") (class "Default")
      (node (ref "R23") (pin "1") (pinfunction "1_1") (pintype "passive"))
      (node (ref "T12") (pin "C") (pinfunction "C_C") (pintype "passive"))
    )
    (net (code "56") (name "Net-(R24-Pad1)") (class "Default")
      (node (ref "R24") (pin "1") (pinfunction "1_1") (pintype "passive"))
      (node (ref "T7") (pin "C") (pinfunction "C_C") (pintype "passive"))
    )
    (net (code "57") (name "Net-(R25-Pad1)") (class "Default")
      (node (ref "R25") (pin "1") (pinfunction "1_1") (pintype "passive"))
      (node (ref "T8") (pin "B") (pinfunction "B_B") (pintype "passive"))
    )
    (net (code "58") (name "Net-(R26-Pad1)") (class "Default")
      (node (ref "R26") (pin "1") (pinfunction "1_1") (pintype "passive"))
      (node (ref "T9") (pin "B") (pinfunction "B_B") (pintype "passive"))
    )
    (net (code "59") (name "Net-(R27-Pad1)") (class "Default")
      (node (ref "R27") (pin "1") (pinfunction "1_1") (pintype "passive"))
      (node (ref "T10") (pin "B") (pinfunction "B_B") (pintype "passive"))
    )
    (net (code "60") (name "Net-(R28-Pad1)") (class "Default")
      (node (ref "R28") (pin "1") (pinfunction "1_1") (pintype "passive"))
      (node (ref "T11") (pin "B") (pinfunction "B_B") (pintype "passive"))
    )
    (net (code "61") (name "Net-(R29-Pad1)") (class "Default")
      (node (ref "R29") (pin "1") (pinfunction "1_1") (pintype "passive"))
      (node (ref "T14") (pin "B") (pinfunction "B_B") (pintype "passive"))
    )
    (net (code "62") (name "Net-(R30-Pad1)") (class "Default")
      (node (ref "R30") (pin "1") (pinfunction "1_1") (pintype "passive"))
      (node (ref "T13") (pin "B") (pinfunction "B_B") (pintype "passive"))
    )
    (net (code "63") (name "Net-(R31-Pad1)") (class "Default")
      (node (ref "R31") (pin "1") (pinfunction "1_1") (pintype "passive"))
      (node (ref "T12") (pin "B") (pinfunction "B_B") (pintype "passive"))
    )
    (net (code "64") (name "Net-(R32-Pad1)") (class "Default")
      (node (ref "R32") (pin "1") (pinfunction "1_1") (pintype "passive"))
      (node (ref "T7") (pin "B") (pinfunction "B_B") (pintype "passive"))
    )
    (net (code "65") (name "Net-(R33-Pad1)") (class "Default")
      (node (ref "R33") (pin "1") (pinfunction "1_1") (pintype "passive"))
      (node (ref "T1") (pin "B") (pinfunction "B_B") (pintype "passive"))
    )
    (net (code "66") (name "Net-(R34-Pad1)") (class "Default")
      (node (ref "R34") (pin "1") (pinfunction "1_1") (pintype "passive"))
      (node (ref "T3") (pin "B") (pinfunction "B_B") (pintype "passive"))
    )
    (net (code "67") (name "Net-(R35-Pad1)") (class "Default")
      (node (ref "R35") (pin "1") (pinfunction "1_1") (pintype "passive"))
      (node (ref "T4") (pin "B") (pinfunction "B_B") (pintype "passive"))
    )
    (net (code "68") (name "Net-(R36-Pad1)") (class "Default")
      (node (ref "R36") (pin "1") (pinfunction "1_1") (pintype "passive"))
      (node (ref "T5") (pin "B") (pinfunction "B_B") (pintype "passive"))
    )
    (net (code "69") (name "Net-(R37-Pad1)") (class "Default")
      (node (ref "R37") (pin "1") (pinfunction "1_1") (pintype "passive"))
      (node (ref "T6") (pin "B") (pinfunction "B_B") (pintype "passive"))
    )
    (net (code "70") (name "Net-(R41-Pad1)") (class "Default")
      (node (ref "R41") (pin "1") (pinfunction "1_1") (pintype "passive"))
      (node (ref "THERM0") (pin "2") (pinfunction "2_2") (pintype "passive"))
    )
    (net (code "71") (name "Net-(R42-Pad1)") (class "Default")
      (node (ref "R42") (pin "1") (pinfunction "1_1") (pintype "passive"))
      (node (ref "THERM0") (pin "1") (pinfunction "1_1") (pintype "passive"))
    )
    (net (code "72") (name "Net-(S2-1)") (class "Default")
      (node (ref "R44") (pin "2") (pinfunction "2_2") (pintype "passive"))
      (node (ref "S2") (pin "A2") (pinfunction "1_A2") (pintype "passive"))
      (node (ref "U1") (pin "94") (pinfunction "AN25/RE1_94") (pintype "bidirectional"))
    )
    (net (code "73") (name "Net-(S3-1)") (class "Default")
      (node (ref "R43") (pin "2") (pinfunction "2_2") (pintype "passive"))
      (node (ref "S3") (pin "A2") (pinfunction "1_A2") (pintype "passive"))
      (node (ref "U1") (pin "98") (pinfunction "AN26/RE2_98") (pintype "bidirectional"))
    )
    (net (code "74") (name "Net-(SW1B-1)") (class "Default")
      (node (ref "R51") (pin "2") (pinfunction "2_2") (pintype "passive"))
      (node (ref "SW1") (pin "P1") (pinfunction "1_P1") (pintype "passive"))
      (node (ref "U1") (pin "97") (pinfunction "CSDO/RG13_97") (pintype "bidirectional"))
    )
    (net (code "75") (name "Net-(T2-D)") (class "Default")
      (node (ref "CONN2") (pin "3") (pinfunction "GND_3") (pintype "bidirectional"))
      (node (ref "CONN2") (pin "6") (pinfunction "GND_6") (pintype "bidirectional"))
      (node (ref "T2") (pin "1") (pinfunction "D_1") (pintype "passive"))
    )
    (net (code "76") (name "Net-(U$1-OSC)") (class "Default")
      (node (ref "U$1") (pin "P$3") (pinfunction "OSC_P$3") (pintype "bidirectional"))
      (node (ref "U1") (pin "63") (pinfunction "OSC1/CLKIN/RC12_63") (pintype "bidirectional"))
    )
    (net (code "77") (name "Net-(U$4-OUT)") (class "Default")
      (node (ref "D1") (pin "C") (pinfunction "C_C") (pintype "passive"))
      (node (ref "L1") (pin "1") (pinfunction "1_1") (pintype "passive"))
      (node (ref "U$4") (pin "8") (pinfunction "OUT_8") (pintype "bidirectional"))
    )
    (net (code "78") (name "Net-(U$5-BAT)") (class "Default")
      (node (ref "U$2") (pin "P$2") (pinfunction "P$1_P$2") (pintype "bidirectional"))
      (node (ref "U$2") (pin "P$3") (pinfunction "P$1_P$3") (pintype "bidirectional"))
      (node (ref "U$5") (pin "6") (pinfunction "BAT_6") (pintype "bidirectional"))
    )
    (net (code "79") (name "Net-(U$5-SCL)") (class "Default")
      (node (ref "R53") (pin "1") (pinfunction "1_1") (pintype "passive"))
      (node (ref "U$5") (pin "8") (pinfunction "SCL_8") (pintype "bidirectional"))
      (node (ref "U1") (pin "58") (pinfunction "SCL2/RA2_58") (pintype "bidirectional"))
    )
    (net (code "80") (name "Net-(U$5-SDA)") (class "Default")
      (node (ref "R45") (pin "1") (pinfunction "1_1") (pintype "passive"))
      (node (ref "U$5") (pin "7") (pinfunction "SDA_7") (pintype "bidirectional"))
      (node (ref "U1") (pin "59") (pinfunction "SDA2/RA3_59") (pintype "bidirectional"))
    )
    (net (code "81") (name "Net-(U$7-AA1)") (class "Default")
      (node (ref "R24") (pin "2") (pinfunction "2_2") (pintype "passive"))
      (node (ref "U$7") (pin "14") (pinfunction "AA1_14") (pintype "bidirectional"))
    )
    (net (code "82") (name "Net-(U$7-AB2)") (class "Default")
      (node (ref "R23") (pin "2") (pinfunction "2_2") (pintype "passive"))
      (node (ref "U$7") (pin "16") (pinfunction "AB2_16") (pintype "bidirectional"))
    )
    (net (code "83") (name "Net-(U$7-AC3)") (class "Default")
      (node (ref "R22") (pin "2") (pinfunction "2_2") (pintype "passive"))
      (node (ref "U$7") (pin "13") (pinfunction "AC3_13") (pintype "bidirectional"))
    )
    (net (code "84") (name "Net-(U$7-AD)") (class "Default")
      (node (ref "R21") (pin "2") (pinfunction "2_2") (pintype "passive"))
      (node (ref "U$7") (pin "3") (pinfunction "AD_3") (pintype "bidirectional"))
    )
    (net (code "85") (name "Net-(U$7-ADP)") (class "Default")
      (node (ref "R17") (pin "2") (pinfunction "2_2") (pintype "passive"))
      (node (ref "U$7") (pin "7") (pinfunction "ADP_7") (pintype "bidirectional"))
    )
    (net (code "86") (name "Net-(U$7-AE)") (class "Default")
      (node (ref "R20") (pin "2") (pinfunction "2_2") (pintype "passive"))
      (node (ref "U$7") (pin "5") (pinfunction "AE_5") (pintype "bidirectional"))
    )
    (net (code "87") (name "Net-(U$7-AF)") (class "Default")
      (node (ref "R19") (pin "2") (pinfunction "2_2") (pintype "passive"))
      (node (ref "U$7") (pin "11") (pinfunction "AF_11") (pintype "bidirectional"))
    )
    (net (code "88") (name "Net-(U$7-AG)") (class "Default")
      (node (ref "R18") (pin "2") (pinfunction "2_2") (pintype "passive"))
      (node (ref "U$7") (pin "15") (pinfunction "AG_15") (pintype "bidirectional"))
    )
    (net (code "89") (name "Net-(U$7-K1)") (class "Default")
      (node (ref "T6") (pin "C") (pinfunction "C_C") (pintype "passive"))
      (node (ref "U$7") (pin "1") (pinfunction "K1_1") (pintype "bidirectional"))
    )
    (net (code "90") (name "Net-(U$7-K2)") (class "Default")
      (node (ref "T5") (pin "C") (pinfunction "C_C") (pintype "passive"))
      (node (ref "U$7") (pin "2") (pinfunction "K2_2") (pintype "bidirectional"))
    )
    (net (code "91") (name "Net-(U$7-K3)") (class "Default")
      (node (ref "T4") (pin "C") (pinfunction "C_C") (pintype "passive"))
      (node (ref "U$7") (pin "6") (pinfunction "K3_6") (pintype "bidirectional"))
    )
    (net (code "92") (name "Net-(U$7-K4)") (class "Default")
      (node (ref "T3") (pin "C") (pinfunction "C_C") (pintype "passive"))
      (node (ref "U$7") (pin "8") (pinfunction "K4_8") (pintype "bidirectional"))
    )
    (net (code "93") (name "Net-(U$7-KL)") (class "Default")
      (node (ref "T1") (pin "C") (pinfunction "C_C") (pintype "passive"))
      (node (ref "U$7") (pin "4") (pinfunction "KL_4") (pintype "bidirectional"))
    )
    (net (code "94") (name "Net-(U$11A-P$2)") (class "Default")
      (node (ref "Q1") (pin "G") (pinfunction "G_G") (pintype "passive"))
      (node (ref "U$11") (pin "7") (pinfunction "P$2_7") (pintype "bidirectional"))
    )
    (net (code "95") (name "Net-(U$11B-P$2)") (class "Default")
      (node (ref "Q2") (pin "G") (pinfunction "G_G") (pintype "passive"))
      (node (ref "U$11") (pin "5") (pinfunction "P$2_5") (pintype "bidirectional"))
    )
    (net (code "96") (name "Net-(U1-AN16{slash}T2CK{slash}T7CK{slash}RC1)") (class "Default")
      (node (ref "LED1") (pin "A") (pinfunction "A_A") (pintype "passive"))
      (node (ref "U1") (pin "6") (pinfunction "AN16/T2CK/T7CK/RC1_6") (pintype "bidirectional"))
    )
    (net (code "97") (name "Net-(U1-AN17{slash}T3CK{slash}T6CK{slash}RC2)") (class "Default")
      (node (ref "LED2") (pin "A") (pinfunction "A_A") (pintype "passive"))
      (node (ref "U1") (pin "7") (pinfunction "AN17/T3CK/T6CK/RC2_7") (pintype "bidirectional"))
    )
    (net (code "98") (name "Net-(U1-AN18{slash}T4CK{slash}T9CK{slash}RC3)") (class "Default")
      (node (ref "LED5") (pin "A") (pinfunction "A_A") (pintype "passive"))
      (node (ref "U1") (pin "8") (pinfunction "AN18/T4CK/T9CK/RC3_8") (pintype "bidirectional"))
    )
    (net (code "99") (name "Net-(U1-AN19{slash}T5CK{slash}T8CK{slash}RC4)") (class "Default")
      (node (ref "LED6") (pin "A") (pinfunction "A_A") (pintype "passive"))
      (node (ref "U1") (pin "9") (pinfunction "AN19/T5CK/T8CK/RC4_9") (pintype "bidirectional"))
    )
    (net (code "100") (name "Net-(U1-CSCK{slash}RG14)") (class "Default")
      (node (ref "R52") (pin "2") (pinfunction "2_2") (pintype "passive"))
      (node (ref "SW1") (pin "B") (pinfunction "B_B") (pintype "passive"))
      (node (ref "U1") (pin "95") (pinfunction "CSCK/RG14_95") (pintype "bidirectional"))
    )
    (net (code "101") (name "Net-(U1-CSDI{slash}RG12)") (class "Default")
      (node (ref "R50") (pin "2") (pinfunction "2_2") (pintype "passive"))
      (node (ref "SW1") (pin "A") (pinfunction "A_A") (pintype "passive"))
      (node (ref "U1") (pin "96") (pinfunction "CSDI/RG12_96") (pintype "bidirectional"))
    )
    (net (code "102") (name "Net-(U1-IC5{slash}RD12)") (class "Default")
      (node (ref "LED4") (pin "C") (pinfunction "C_C") (pintype "passive"))
      (node (ref "U1") (pin "79") (pinfunction "IC5/RD12_79") (pintype "bidirectional"))
    )
    (net (code "103") (name "Net-(U1-IC6{slash}CN19{slash}RD13)") (class "Default")
      (node (ref "LED3") (pin "C") (pinfunction "C_C") (pintype "passive"))
      (node (ref "U1") (pin "80") (pinfunction "IC6/CN19/RD13_80") (pintype "bidirectional"))
    )
    (net (code "104") (name "Net-(U1-VCAP)") (class "Default")
      (node (ref "C10") (pin "1") (pinfunction "1_1") (pintype "passive"))
      (node (ref "U1") (pin "85") (pinfunction "VCAP_85") (pintype "bidirectional"))
    )
    (net (code "105") (name "Net-(U2-+IN)") (class "Default")
      (node (ref "C14") (pin "1") (pinfunction "1_1") (pintype "passive"))
      (node (ref "C19") (pin "2") (pinfunction "2_2") (pintype "passive"))
      (node (ref "R42") (pin "2") (pinfunction "2_2") (pintype "passive"))
      (node (ref "U2") (pin "8") (pinfunction "+IN_8") (pintype "bidirectional"))
    )
    (net (code "106") (name "Net-(U2--IN)") (class "Default")
      (node (ref "C14") (pin "2") (pinfunction "2_2") (pintype "passive"))
      (node (ref "C20") (pin "1") (pinfunction "1_1") (pintype "passive"))
      (node (ref "R40") (pin "1") (pinfunction "1_1") (pintype "passive"))
      (node (ref "R41") (pin "2") (pinfunction "2_2") (pintype "passive"))
      (node (ref "U2") (pin "1") (pinfunction "-IN_1") (pintype "bidirectional"))
    )
    (net (code "107") (name "Net-(U2-SENSE)") (class "Default")
      (node (ref "SJ1") (pin "1") (pinfunction "1_1") (pintype "passive"))
      (node (ref "U2") (pin "5") (pinfunction "SENSE_5") (pintype "bidirectional"))
    )
    (net (code "108") (name "OE") (class "Default")
      (node (ref "U1") (pin "39") (pinfunction "U2RTS/RF13_39") (pintype "bidirectional"))
    )
    (net (code "109") (name "PGC1") (class "Default")
      (node (ref "CPU") (pin "5") (pinfunction "5_5") (pintype "passive"))
      (node (ref "U1") (pin "74") (pinfunction "PGEDC/SOSCO/T1CK/CN0/RC14_74") (pintype "bidirectional"))
    )
    (net (code "110") (name "PGD1") (class "Default")
      (node (ref "CPU") (pin "4") (pinfunction "4_4") (pintype "passive"))
      (node (ref "U1") (pin "73") (pinfunction "PGED2/SOSCI/CN1/RC13_73") (pintype "bidirectional"))
    )
    (net (code "111") (name "RST_INT") (class "Default")
      (node (ref "U$5") (pin "4") (pinfunction "~{RST}_4") (pintype "bidirectional"))
      (node (ref "U1") (pin "19") (pinfunction "AN21/INT2/RA13_19") (pintype "bidirectional"))
    )
    (net (code "112") (name "RTC_INT") (class "Default")
      (node (ref "R54") (pin "1") (pinfunction "1_1") (pintype "passive"))
      (node (ref "U$5") (pin "3") (pinfunction "~{INT}_3") (pintype "bidirectional"))
      (node (ref "U1") (pin "18") (pinfunction "AN20/INT1/RA12_18") (pintype "bidirectional"))
    )
    (net (code "113") (name "RTS") (class "Default")
      (node (ref "FTDI") (pin "6") (pinfunction "6_6") (pintype "passive"))
      (node (ref "IC1") (pin "3") (pinfunction "~{RTS}_3") (pintype "output"))
    )
    (net (code "114") (name "RX") (class "Default")
      (node (ref "FTDI") (pin "5") (pinfunction "5_5") (pintype "passive"))
      (node (ref "IC1") (pin "5") (pinfunction "RXD_5") (pintype "input"))
      (node (ref "U1") (pin "51") (pinfunction "U1TX/RF3_51") (pintype "bidirectional"))
    )
    (net (code "115") (name "SCK1") (class "Default")
      (node (ref "CONN2") (pin "5") (pinfunction "CLK_5") (pintype "bidirectional"))
      (node (ref "R11") (pin "1") (pinfunction "1_1") (pintype "passive"))
      (node (ref "U1") (pin "55") (pinfunction "SCK1/INT0/RF6_55") (pintype "bidirectional"))
    )
    (net (code "116") (name "SCK2") (class "Default")
      (node (ref "U1") (pin "10") (pinfunction "SCK2/CN8/RG6_10") (pintype "bidirectional"))
    )
    (net (code "117") (name "SDI1") (class "Default")
      (node (ref "CONN2") (pin "7") (pinfunction "SDO_7") (pintype "bidirectional"))
      (node (ref "R10") (pin "1") (pinfunction "1_1") (pintype "passive"))
      (node (ref "U1") (pin "54") (pinfunction "SDI1/RF7_54") (pintype "bidirectional"))
    )
    (net (code "118") (name "SDI2") (class "Default")
      (node (ref "U1") (pin "11") (pinfunction "SDI2/CN9/RG7_11") (pintype "bidirectional"))
    )
    (net (code "119") (name "SDO1") (class "Default")
      (node (ref "CONN2") (pin "2") (pinfunction "SDI_2") (pintype "bidirectional"))
      (node (ref "R9") (pin "1") (pinfunction "1_1") (pintype "passive"))
      (node (ref "U1") (pin "53") (pinfunction "SDO1/RF8_53") (pintype "bidirectional"))
    )
    (net (code "120") (name "SD_PWR") (class "Default")
      (node (ref "R16") (pin "1") (pinfunction "1_1") (pintype "passive"))
      (node (ref "U1") (pin "67") (pinfunction "INT4/RA15_67") (pintype "bidirectional"))
    )
    (net (code "121") (name "T0") (class "Default")
      (node (ref "SJ1") (pin "2") (pinfunction "2_2") (pintype "passive"))
      (node (ref "U1") (pin "22") (pinfunction "AN3/CN5/RB3_22") (pintype "bidirectional"))
      (node (ref "U2") (pin "6") (pinfunction "OUT_6") (pintype "bidirectional"))
    )
    (net (code "122") (name "T1") (class "Default")
      (node (ref "C11") (pin "1") (pinfunction "1_1") (pintype "passive"))
      (node (ref "R38") (pin "2") (pinfunction "2_2") (pintype "passive"))
      (node (ref "THERM1") (pin "2") (pinfunction "2_2") (pintype "passive"))
      (node (ref "U1") (pin "21") (pinfunction "AN4/CN6/RB4_21") (pintype "bidirectional"))
    )
    (net (code "123") (name "T2") (class "Default")
      (node (ref "C13") (pin "1") (pinfunction "1_1") (pintype "passive"))
      (node (ref "R39") (pin "2") (pinfunction "2_2") (pintype "passive"))
      (node (ref "THERM2") (pin "2") (pinfunction "2_2") (pintype "passive"))
      (node (ref "U1") (pin "20") (pinfunction "AN5/CN7/RB5_20") (pintype "bidirectional"))
    )
    (net (code "124") (name "TX") (class "Default")
      (node (ref "FTDI") (pin "4") (pinfunction "4_4") (pintype "passive"))
      (node (ref "R5") (pin "1") (pinfunction "1_1") (pintype "passive"))
      (node (ref "U1") (pin "52") (pinfunction "U1RX/RF2_52") (pintype "bidirectional"))
    )
    (net (code "125") (name "VDD") (class "Default")
      (node (ref "C1") (pin "+") (pinfunction "+_+") (pintype "passive"))
      (node (ref "C12") (pin "1") (pinfunction "1_1") (pintype "passive"))
      (node (ref "C15") (pin "1") (pinfunction "1_1") (pintype "passive"))
      (node (ref "C16") (pin "1") (pinfunction "1_1") (pintype "passive"))
      (node (ref "C17") (pin "1") (pinfunction "1_1") (pintype "passive"))
      (node (ref "C18") (pin "1") (pinfunction "1_1") (pintype "passive"))
      (node (ref "C3") (pin "1") (pinfunction "1_1") (pintype "passive"))
      (node (ref "C7") (pin "1") (pinfunction "1_1") (pintype "passive"))
      (node (ref "CONN2") (pin "4") (pinfunction "VCC_4") (pintype "bidirectional"))
      (node (ref "CPU") (pin "2") (pinfunction "2_2") (pintype "passive"))
      (node (ref "L1") (pin "2") (pinfunction "2_2") (pintype "passive"))
      (node (ref "R10") (pin "2") (pinfunction "2_2") (pintype "passive"))
      (node (ref "R11") (pin "2") (pinfunction "2_2") (pintype "passive"))
      (node (ref "R12") (pin "2") (pinfunction "2_2") (pintype "passive"))
      (node (ref "R13") (pin "2") (pinfunction "2_2") (pintype "passive"))
      (node (ref "R43") (pin "1") (pinfunction "1_1") (pintype "passive"))
      (node (ref "R44") (pin "1") (pinfunction "1_1") (pintype "passive"))
      (node (ref "R45") (pin "2") (pinfunction "2_2") (pintype "passive"))
      (node (ref "R50") (pin "1") (pinfunction "1_1") (pintype "passive"))
      (node (ref "R51") (pin "1") (pinfunction "1_1") (pintype "passive"))
      (node (ref "R52") (pin "1") (pinfunction "1_1") (pintype "passive"))
      (node (ref "R53") (pin "2") (pinfunction "2_2") (pintype "passive"))
      (node (ref "R54") (pin "2") (pinfunction "2_2") (pintype "passive"))
      (node (ref "R7") (pin "2") (pinfunction "2_2") (pintype "passive"))
      (node (ref "R8") (pin "2") (pinfunction "2_2") (pintype "passive"))
      (node (ref "R9") (pin "2") (pinfunction "2_2") (pintype "passive"))
      (node (ref "T10") (pin "E") (pinfunction "E_E") (pintype "passive"))
      (node (ref "T11") (pin "E") (pinfunction "E_E") (pintype "passive"))
      (node (ref "T12") (pin "E") (pinfunction "E_E") (pintype "passive"))
      (node (ref "T13") (pin "E") (pinfunction "E_E") (pintype "passive"))
      (node (ref "T14") (pin "E") (pinfunction "E_E") (pintype "passive"))
      (node (ref "T7") (pin "E") (pinfunction "E_E") (pintype "passive"))
      (node (ref "T8") (pin "E") (pinfunction "E_E") (pintype "passive"))
      (node (ref "T9") (pin "E") (pinfunction "E_E") (pintype "passive"))
      (node (ref "U$1") (pin "P$4") (pinfunction "VCC_P$4") (pintype "bidirectional"))
      (node (ref "U$4") (pin "4") (pinfunction "FB_4") (pintype "bidirectional"))
      (node (ref "U$5") (pin "2") (pinfunction "VCC_2") (pintype "bidirectional"))
      (node (ref "U1") (pin "16") (pinfunction "VDD_16") (pintype "bidirectional"))
      (node (ref "U1") (pin "2") (pinfunction "VDD_2") (pintype "bidirectional"))
      (node (ref "U1") (pin "30") (pinfunction "AVDD_30") (pintype "bidirectional"))
      (node (ref "U1") (pin "37") (pinfunction "VDD_37") (pintype "bidirectional"))
      (node (ref "U1") (pin "46") (pinfunction "VDD_46") (pintype "bidirectional"))
      (node (ref "U1") (pin "62") (pinfunction "VDD_62") (pintype "bidirectional"))
      (node (ref "U1") (pin "86") (pinfunction "VDD_86") (pintype "bidirectional"))
      (node (ref "U2") (pin "7") (pinfunction "+VS_7") (pintype "bidirectional"))
    )
    (net (code "126") (name "WE") (class "Default")
      (node (ref "U1") (pin "40") (pinfunction "U2CTS/RF12_40") (pintype "bidirectional"))
    )
    (net (code "127") (name "unconnected-(CN1-PadID)") (class "Default")
      (node (ref "CN1") (pin "ID") (pinfunction "ID_ID") (pintype "bidirectional"))
    )
    (net (code "128") (name "unconnected-(IC1-CBUS2-Pad13)") (class "Default")
      (node (ref "IC1") (pin "13") (pinfunction "CBUS2_13") (pintype "bidirectional"))
    )
    (net (code "129") (name "unconnected-(IC1-CBUS3-Pad14)") (class "Default")
      (node (ref "IC1") (pin "14") (pinfunction "CBUS3_14") (pintype "bidirectional"))
    )
    (net (code "130") (name "unconnected-(IC1-CBUS4-Pad12)") (class "Default")
      (node (ref "IC1") (pin "12") (pinfunction "CBUS4_12") (pintype "bidirectional"))
    )
    (net (code "131") (name "unconnected-(IC1-OSCI-Pad27)") (class "Default")
      (node (ref "IC1") (pin "27") (pinfunction "OSCI_27") (pintype "input"))
    )
    (net (code "132") (name "unconnected-(IC1-OSCO-Pad28)") (class "Default")
      (node (ref "IC1") (pin "28") (pinfunction "OSCO_28") (pintype "output"))
    )
    (net (code "133") (name "unconnected-(IC1-~{DCD}-Pad10)") (class "Default")
      (node (ref "IC1") (pin "10") (pinfunction "~{DCD}_10") (pintype "input"))
    )
    (net (code "134") (name "unconnected-(IC1-~{DSR}-Pad9)") (class "Default")
      (node (ref "IC1") (pin "9") (pinfunction "~{DSR}_9") (pintype "input"))
    )
    (net (code "135") (name "unconnected-(IC1-~{RESET}-Pad19)") (class "Default")
      (node (ref "IC1") (pin "19") (pinfunction "~{RESET}_19") (pintype "input"))
    )
    (net (code "136") (name "unconnected-(IC1-~{RI}-Pad6)") (class "Default")
      (node (ref "IC1") (pin "6") (pinfunction "~{RI}_6") (pintype "input"))
    )
    (net (code "137") (name "unconnected-(IC2-OPT-Pad3)") (class "Default")
      (node (ref "IC2") (pin "3") (pinfunction "OPT_3") (pintype "output"))
    )
    (net (code "138") (name "unconnected-(IC2-TRM-Pad5)") (class "Default")
      (node (ref "IC2") (pin "5") (pinfunction "TRM_5") (pintype "input"))
    )
    (net (code "139") (name "unconnected-(U$4-NC-Pad1)") (class "Default")
      (node (ref "U$4") (pin "1") (pinfunction "NC_1") (pintype "bidirectional"))
    )
    (net (code "140") (name "unconnected-(U$4-NC-Pad2)") (class "Default")
      (node (ref "U$4") (pin "2") (pinfunction "NC_2") (pintype "bidirectional"))
    )
    (net (code "141") (name "unconnected-(U$4-NC-Pad3)") (class "Default")
      (node (ref "U$4") (pin "3") (pinfunction "NC_3") (pintype "bidirectional"))
    )
    (net (code "142") (name "unconnected-(U$5-32KHZ-Pad1)") (class "Default")
      (node (ref "U$5") (pin "1") (pinfunction "32KHZ_1") (pintype "bidirectional"))
    )
    (net (code "143") (name "unconnected-(U1-AN8{slash}RB8-Pad32)") (class "Default")
      (node (ref "U1") (pin "32") (pinfunction "AN8/RB8_32") (pintype "bidirectional"))
    )
    (net (code "144") (name "unconnected-(U1-AN9{slash}RB9-Pad33)") (class "Default")
      (node (ref "U1") (pin "33") (pinfunction "AN9/RB9_33") (pintype "bidirectional"))
    )
    (net (code "145") (name "unconnected-(U1-AN10{slash}RB10-Pad34)") (class "Default")
      (node (ref "U1") (pin "34") (pinfunction "AN10/RB10_34") (pintype "bidirectional"))
    )
    (net (code "146") (name "unconnected-(U1-AN11{slash}RB11-Pad35)") (class "Default")
      (node (ref "U1") (pin "35") (pinfunction "AN11/RB11_35") (pintype "bidirectional"))
    )
    (net (code "147") (name "unconnected-(U1-AN12{slash}RB12-Pad41)") (class "Default")
      (node (ref "U1") (pin "41") (pinfunction "AN12/RB12_41") (pintype "bidirectional"))
    )
    (net (code "148") (name "unconnected-(U1-AN13{slash}RB13-Pad42)") (class "Default")
      (node (ref "U1") (pin "42") (pinfunction "AN13/RB13_42") (pintype "bidirectional"))
    )
    (net (code "149") (name "unconnected-(U1-AN14{slash}RB14-Pad43)") (class "Default")
      (node (ref "U1") (pin "43") (pinfunction "AN14/RB14_43") (pintype "bidirectional"))
    )
    (net (code "150") (name "unconnected-(U1-AN15{slash}OCFB{slash}CN12{slash}RB15-Pad44)") (class "Default")
      (node (ref "U1") (pin "44") (pinfunction "AN15/OCFB/CN12/RB15_44") (pintype "bidirectional"))
    )
    (net (code "151") (name "unconnected-(U1-AN22{slash}CN22{slash}RA6-Pad91)") (class "Default")
      (node (ref "U1") (pin "91") (pinfunction "AN22/CN22/RA6_91") (pintype "bidirectional"))
    )
    (net (code "152") (name "unconnected-(U1-AN23{slash}CN23{slash}RA7-Pad92)") (class "Default")
      (node (ref "U1") (pin "92") (pinfunction "AN23/CN23/RA7_92") (pintype "bidirectional"))
    )
    (net (code "153") (name "unconnected-(U1-AN24{slash}RE0-Pad93)") (class "Default")
      (node (ref "U1") (pin "93") (pinfunction "AN24/RE0_93") (pintype "bidirectional"))
    )
    (net (code "154") (name "unconnected-(U1-AN31{slash}RE7-Pad5)") (class "Default")
      (node (ref "U1") (pin "5") (pinfunction "AN31/RE7_5") (pintype "bidirectional"))
    )
    (net (code "155") (name "unconnected-(U1-C1RX{slash}RF0-Pad87)") (class "Default")
      (node (ref "U1") (pin "87") (pinfunction "C1RX/RF0_87") (pintype "bidirectional"))
    )
    (net (code "156") (name "unconnected-(U1-C1TX{slash}RF1-Pad88)") (class "Default")
      (node (ref "U1") (pin "88") (pinfunction "C1TX/RF1_88") (pintype "bidirectional"))
    )
    (net (code "157") (name "unconnected-(U1-COFS{slash}RG15-Pad1)") (class "Default")
      (node (ref "U1") (pin "1") (pinfunction "COFS/RG15_1") (pintype "bidirectional"))
    )
    (net (code "158") (name "unconnected-(U1-IC1{slash}RD8-Pad68)") (class "Default")
      (node (ref "U1") (pin "68") (pinfunction "IC1/RD8_68") (pintype "bidirectional"))
    )
    (net (code "159") (name "unconnected-(U1-IC2{slash}RD9-Pad69)") (class "Default")
      (node (ref "U1") (pin "69") (pinfunction "IC2/RD9_69") (pintype "bidirectional"))
    )
    (net (code "160") (name "unconnected-(U1-IC3{slash}RD10-Pad70)") (class "Default")
      (node (ref "U1") (pin "70") (pinfunction "IC3/RD10_70") (pintype "bidirectional"))
    )
    (net (code "161") (name "unconnected-(U1-IC4{slash}RD11-Pad71)") (class "Default")
      (node (ref "U1") (pin "71") (pinfunction "IC4/RD11_71") (pintype "bidirectional"))
    )
    (net (code "162") (name "unconnected-(U1-IC7{slash}U1CTS{slash}CN20{slash}RD14-Pad47)") (class "Default")
      (node (ref "U1") (pin "47") (pinfunction "IC7/U1CTS/CN20/RD14_47") (pintype "bidirectional"))
    )
    (net (code "163") (name "unconnected-(U1-IC8{slash}U1RTS{slash}CN21{slash}RD15-Pad48)") (class "Default")
      (node (ref "U1") (pin "48") (pinfunction "IC8/U1RTS/CN21/RD15_48") (pintype "bidirectional"))
    )
    (net (code "164") (name "unconnected-(U1-INT3{slash}RA14-Pad66)") (class "Default")
      (node (ref "U1") (pin "66") (pinfunction "INT3/RA14_66") (pintype "bidirectional"))
    )
    (net (code "165") (name "unconnected-(U1-PGEC1{slash}AN6{slash}OCFA{slash}RB6-Pad26)") (class "Default")
      (node (ref "U1") (pin "26") (pinfunction "PGEC1/AN6/OCFA/RB6_26") (pintype "bidirectional"))
    )
    (net (code "166") (name "unconnected-(U1-PGED1{slash}AN7{slash}RB7-Pad27)") (class "Default")
      (node (ref "U1") (pin "27") (pinfunction "PGED1/AN7/RB7_27") (pintype "bidirectional"))
    )
    (net (code "167") (name "unconnected-(U1-RG0-Pad90)") (class "Default")
      (node (ref "U1") (pin "90") (pinfunction "RG0_90") (pintype "bidirectional"))
    )
    (net (code "168") (name "unconnected-(U1-RG1-Pad89)") (class "Default")
      (node (ref "U1") (pin "89") (pinfunction "RG1_89") (pintype "bidirectional"))
    )
    (net (code "169") (name "unconnected-(U1-SCL1{slash}RG2-Pad57)") (class "Default")
      (node (ref "U1") (pin "57") (pinfunction "SCL1/RG2_57") (pintype "bidirectional"))
    )
    (net (code "170") (name "unconnected-(U1-SS2{slash}CN11{slash}RG9-Pad14)") (class "Default")
      (node (ref "U1") (pin "14") (pinfunction "SS2/CN11/RG9_14") (pintype "bidirectional"))
    )
    (net (code "171") (name "unconnected-(U1-TDI{slash}RA4-Pad60)") (class "Default")
      (node (ref "U1") (pin "60") (pinfunction "TDI/RA4_60") (pintype "bidirectional"))
    )
    (net (code "172") (name "unconnected-(U1-TDO{slash}RA5-Pad61)") (class "Default")
      (node (ref "U1") (pin "61") (pinfunction "TDO/RA5_61") (pintype "bidirectional"))
    )
    (net (code "173") (name "unconnected-(U1-TMS{slash}RA0-Pad17)") (class "Default")
      (node (ref "U1") (pin "17") (pinfunction "TMS/RA0_17") (pintype "bidirectional"))
    )
    (net (code "174") (name "unconnected-(U1-U2RX{slash}CN17{slash}RF4-Pad49)") (class "Default")
      (node (ref "U1") (pin "49") (pinfunction "U2RX/CN17/RF4_49") (pintype "bidirectional"))
    )
    (net (code "175") (name "unconnected-(U1-U2TX{slash}CN18{slash}RF5-Pad50)") (class "Default")
      (node (ref "U1") (pin "50") (pinfunction "U2TX/CN18/RF5_50") (pintype "bidirectional"))
    )
    (net (code "176") (name "unconnected-(U2-NC-Pad4)") (class "Default")
      (node (ref "U2") (pin "4") (pinfunction "NC_4") (pintype "bidirectional"))
    )
  )
)
